# DUAL_POWER_SUPPLY.net
KiCad netlist of a schematic drawn in EAGLE
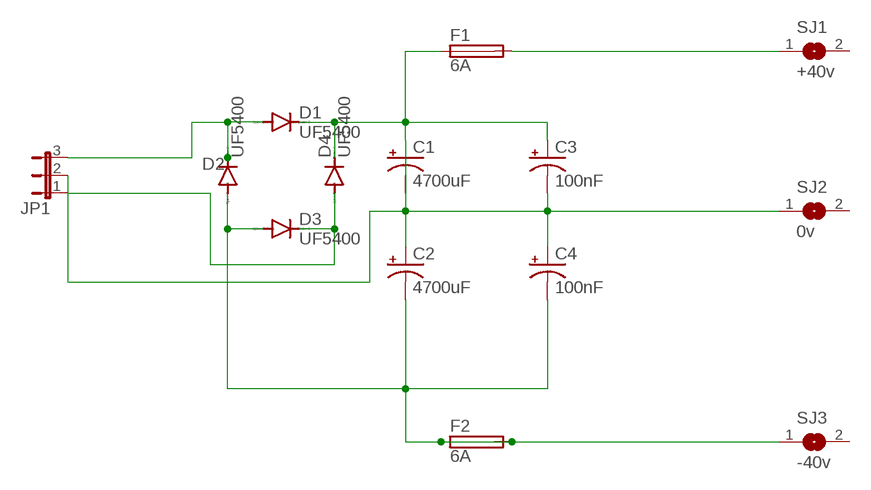
[diagram p0: schematic, sheet 1]

(export (version "E")
  (design (tool "Eeschema 10.0.6"))
  (components
    (comp (ref "C1")
      (value "4700uF")
      (footprint "eagle-import:175TMP-0808")
      (libsource (lib "eagle-import") (part "CPOL-US175TMP-0808"))
    )
    (comp (ref "C2")
      (value "4700uF")
      (footprint "eagle-import:175TMP-0808")
      (libsource (lib "eagle-import") (part "CPOL-US175TMP-0808"))
    )
    (comp (ref "C3")
      (value "100nF")
      (footprint "eagle-import:175TMP-0808")
      (libsource (lib "eagle-import") (part "CPOL-US175TMP-0808"))
    )
    (comp (ref "C4")
      (value "100nF")
      (footprint "eagle-import:175TMP-0808")
      (libsource (lib "eagle-import") (part "CPOL-US175TMP-0808"))
    )
    (comp (ref "D1")
      (value "UF5400")
      (footprint "eagle-import:DO201-15")
      (libsource (lib "eagle-import") (part "UF5400"))
    )
    (comp (ref "D2")
      (value "UF5400")
      (footprint "eagle-import:DO201-15")
      (libsource (lib "eagle-import") (part "UF5400"))
    )
    (comp (ref "D3")
      (value "UF5400")
      (footprint "eagle-import:DO201-15")
      (libsource (lib "eagle-import") (part "UF5400"))
    )
    (comp (ref "D4")
      (value "UF5400")
      (footprint "eagle-import:DO201-15")
      (libsource (lib "eagle-import") (part "UF5400"))
    )
    (comp (ref "F1")
      (value "6A")
      (footprint "eagle-import:19560")
      (fields (field (name "MPN") "56000001009"))
      (libsource (lib "eagle-import") (part "19560"))
    )
    (comp (ref "F2")
      (value "6A")
      (footprint "eagle-import:19560")
      (fields (field (name "MPN") "56000001009"))
      (libsource (lib "eagle-import") (part "19560"))
    )
    (comp (ref "JP1")
      (value "JP2W")
      (footprint "eagle-import:JP2W")
      (libsource (lib "eagle-import") (part "JP2W"))
    )
    (comp (ref "SJ1")
      (value "+40v")
      (footprint "eagle-import:SJW")
      (libsource (lib "eagle-import") (part "SJW"))
    )
    (comp (ref "SJ2")
      (value "0v")
      (footprint "eagle-import:SJW")
      (libsource (lib "eagle-import") (part "SJW"))
    )
    (comp (ref "SJ3")
      (value "-40v")
      (footprint "eagle-import:SJW")
      (libsource (lib "eagle-import") (part "SJW"))
    )
  )
  (nets
    (net (code "1") (name "Net-(C1-Pad+)") (class "Default")
      (node (ref "C1") (pin "+") (pinfunction "+_+") (pintype "passive"))
      (node (ref "C1") (pin "-") (pinfunction "-_-") (pintype "passive"))
      (node (ref "C2") (pin "+") (pinfunction "+_+") (pintype "passive"))
      (node (ref "C3") (pin "+") (pinfunction "+_+") (pintype "passive"))
      (node (ref "C3") (pin "-") (pinfunction "-_-") (pintype "passive"))
      (node (ref "C4") (pin "+") (pinfunction "+_+") (pintype "passive"))
      (node (ref "D1") (pin "C") (pinfunction "C_C") (pintype "passive"))
      (node (ref "D4") (pin "C") (pinfunction "C_C") (pintype "passive"))
      (node (ref "F1") (pin "1") (pinfunction "1_1") (pintype "passive"))
      (node (ref "JP1") (pin "2") (pinfunction "2_2") (pintype "passive"))
      (node (ref "SJ2") (pin "1") (pinfunction "1_1") (pintype "passive"))
    )
    (net (code "2") (name "Net-(C2-Pad-)") (class "Default")
      (node (ref "C2") (pin "-") (pinfunction "-_-") (pintype "passive"))
      (node (ref "C4") (pin "-") (pinfunction "-_-") (pintype "passive"))
      (node (ref "D2") (pin "A") (pinfunction "A_A") (pintype "passive"))
      (node (ref "D3") (pin "A") (pinfunction "A_A") (pintype "passive"))
      (node (ref "F2") (pin "1") (pinfunction "1_1") (pintype "passive"))
      (node (ref "F2") (pin "2") (pinfunction "2_2") (pintype "passive"))
      (node (ref "SJ3") (pin "1") (pinfunction "1_1") (pintype "passive"))
    )
    (net (code "3") (name "Net-(D1-PadA)") (class "Default")
      (node (ref "D1") (pin "A") (pinfunction "A_A") (pintype "passive"))
      (node (ref "D2") (pin "C") (pinfunction "C_C") (pintype "passive"))
      (node (ref "JP1") (pin "3") (pinfunction "3_3") (pintype "passive"))
    )
    (net (code "4") (name "Net-(D3-PadC)") (class "Default")
      (node (ref "D3") (pin "C") (pinfunction "C_C") (pintype "passive"))
      (node (ref "D4") (pin "A") (pinfunction "A_A") (pintype "passive"))
      (node (ref "JP1") (pin "1") (pinfunction "1_1") (pintype "passive"))
    )
    (net (code "5") (name "Net-(F1-Pad2)") (class "Default")
      (node (ref "F1") (pin "2") (pinfunction "2_2") (pintype "passive"))
      (node (ref "SJ1") (pin "1") (pinfunction "1_1") (pintype "passive"))
    )
    (net (code "6") (name "unconnected-(SJ1-Pad2)") (class "Default")
      (node (ref "SJ1") (pin "2") (pinfunction "2_2") (pintype "passive"))
    )
    (net (code "7") (name "unconnected-(SJ2-Pad2)") (class "Default")
      (node (ref "SJ2") (pin "2") (pinfunction "2_2") (pintype "passive"))
    )
    (net (code "8") (name "unconnected-(SJ3-Pad2)") (class "Default")
      (node (ref "SJ3") (pin "2") (pinfunction "2_2") (pintype "passive"))
    )
  )
)
